# I2C_DP_Sensor_3.net
KiCad netlist of a schematic drawn in Altium Designer
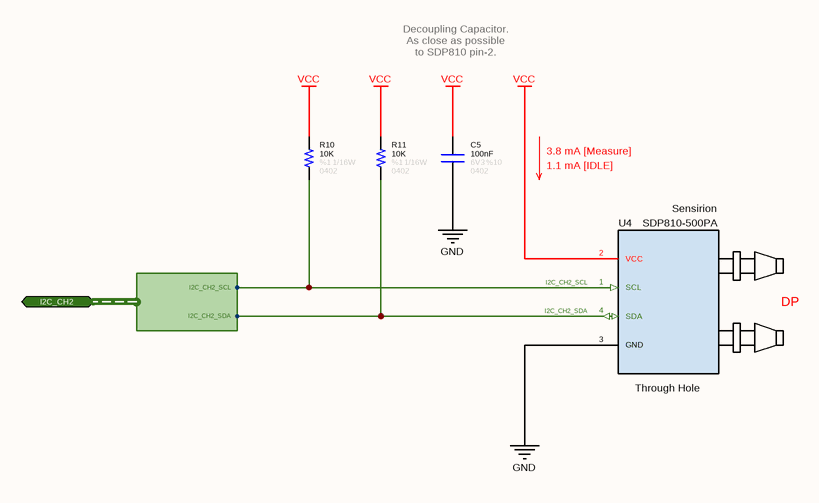
[diagram p0: I2C DP Sensor 3.SchDoc]

(export (version "E")
  (design (tool "Eeschema 10.0.6"))
  (components
    (comp (ref "C5")
      (value "100nF")
      (footprint "CAPACITOR_0402")
      (description "Capacitor - 100nF [0402-6V3] (Ceramic)")
      (fields
        (field (name "MANUFACTURER PART NUMBER") "04026D104KAT4A")
        (field (name "TOLERANCE") "%10")
        (field (name "VOLTAGE") "6V3")
        (field (name "CASE") "0402")
        (field (name "Comment") "Capacitor - 100nF [0402] (Ceramic)")
      )
      (libsource (lib "P101DA_Library") (part "Capacitor - 100nF [0402-6V3]"))
    )
    (comp (ref "R10")
      (value "10K")
      (footprint "RESISTOR_0402")
      (description "Thick Film Resistors - SMD 1/16 W 10 KOhm 1%")
      (fields
        (field (name "MANUFACTURER PART NUMBER") "CRCW040210K0FKED")
        (field (name "TOLERANCE") "%1")
        (field (name "CASE") "0402")
        (field (name "POWER") "1/16W")
        (field (name "Comment") "10K - 0402 - %1 - 1/16W")
      )
      (libsource (lib "P101DA_Library") (part "Resistor - 10K [0402]"))
    )
    (comp (ref "R11")
      (value "10K")
      (footprint "RESISTOR_0402")
      (description "Thick Film Resistors - SMD 1/16 W 10 KOhm 1%")
      (fields
        (field (name "MANUFACTURER PART NUMBER") "CRCW040210K0FKED")
        (field (name "TOLERANCE") "%1")
        (field (name "CASE") "0402")
        (field (name "POWER") "1/16W")
        (field (name "Comment") "10K - 0402 - %1 - 1/16W")
      )
      (libsource (lib "P101DA_Library") (part "Resistor - 10K [0402]"))
    )
    (comp (ref "U4")
      (value "SDP810-500PA")
      (footprint "SDP810-500PA")
      (description "Board Mount Pressure Sensors Tube Connection, I2C , 500Pa")
      (fields
        (field (name "MANUFACTURER NAME") "Sensirion")
        (field (name "MANUFACTURER PART NUMBER") "SDP810-500PA")
        (field (name "CASE") "Through Hole")
      )
      (libsource (lib "P101DA_Library") (part "IC - SDP810-500PA"))
    )
  )
  (nets
    (net (code "2") (name "/I2C_CH2_SCL") (class "Default")
      (node (ref "R10") (pin "1") (pinfunction "1_1") (pintype "passive"))
      (node (ref "U4") (pin "1") (pinfunction "SCL_1") (pintype "input"))
    )
    (net (code "3") (name "/I2C_CH2_SDA") (class "Default")
      (node (ref "R11") (pin "1") (pinfunction "1_1") (pintype "passive"))
      (node (ref "U4") (pin "4") (pinfunction "SDA_4") (pintype "bidirectional"))
    )
    (net (code "5") (name "GND") (class "Default")
      (node (ref "C5") (pin "1") (pinfunction "1_1") (pintype "passive"))
      (node (ref "U4") (pin "3") (pinfunction "GND_3") (pintype "passive"))
    )
    (net (code "6") (name "VCC") (class "Default")
      (node (ref "C5") (pin "2") (pinfunction "2_2") (pintype "passive"))
      (node (ref "R10") (pin "2") (pinfunction "2_2") (pintype "passive"))
      (node (ref "R11") (pin "2") (pinfunction "2_2") (pintype "passive"))
      (node (ref "U4") (pin "2") (pinfunction "VCC_2") (pintype "power_in"))
    )
  )
)
